# AlarisHandV1.net
KiCad netlist of a schematic drawn in EAGLE
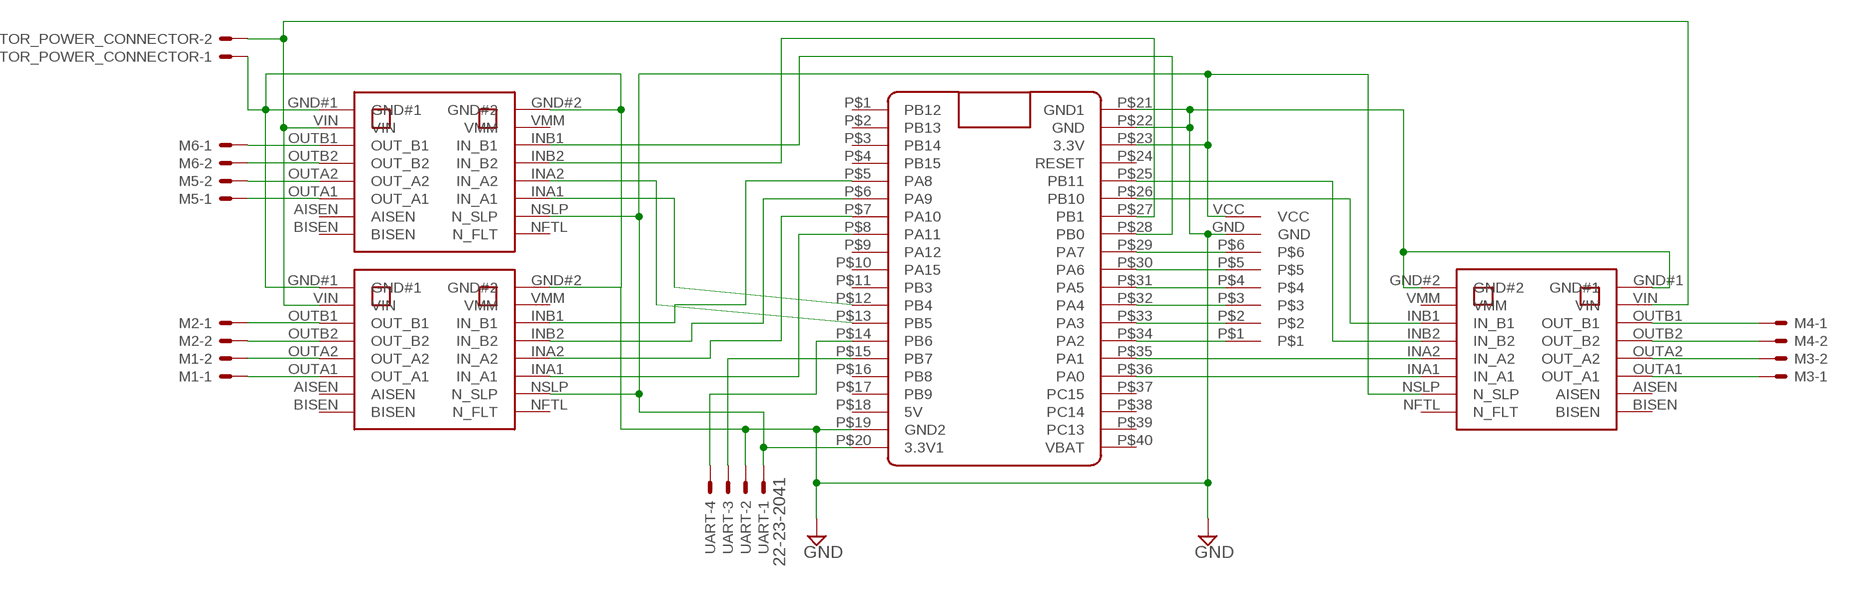
[diagram p0: schematic, sheet 1]

(export (version "E")
  (design (tool "Eeschema 10.0.6"))
  (components
    (comp (ref "M1")
      (value "22-23-2021")
      (footprint "eagle-import:22-23-2021")
      (fields (field (name "MF") "MOLEX"))
      (libsource (lib "eagle-import") (part "22-23-2021"))
    )
    (comp (ref "M2")
      (value "22-23-2021")
      (footprint "eagle-import:22-23-2021")
      (fields (field (name "MF") "MOLEX"))
      (libsource (lib "eagle-import") (part "22-23-2021"))
    )
    (comp (ref "M3")
      (value "22-23-2021")
      (footprint "eagle-import:22-23-2021")
      (fields (field (name "MF") "MOLEX"))
      (libsource (lib "eagle-import") (part "22-23-2021"))
    )
    (comp (ref "M4")
      (value "22-23-2021")
      (footprint "eagle-import:22-23-2021")
      (fields (field (name "MF") "MOLEX"))
      (libsource (lib "eagle-import") (part "22-23-2021"))
    )
    (comp (ref "M5")
      (value "22-23-2021")
      (footprint "eagle-import:22-23-2021")
      (fields (field (name "MF") "MOLEX"))
      (libsource (lib "eagle-import") (part "22-23-2021"))
    )
    (comp (ref "M6")
      (value "22-23-2021")
      (footprint "eagle-import:22-23-2021")
      (fields (field (name "MF") "MOLEX"))
      (libsource (lib "eagle-import") (part "22-23-2021"))
    )
    (comp (ref "MOTOR_POWER_CONNECTOR")
      (value "22-23-2021")
      (footprint "eagle-import:22-23-2021")
      (fields (field (name "MF") "MOLEX"))
      (libsource (lib "eagle-import") (part "con-molex_165_22-23-2021"))
    )
    (comp (ref "U$1")
      (value "POLOLUDRV8833")
      (footprint "eagle-import:POLOLUDRV8833")
      (libsource (lib "eagle-import") (part "POLOLUDRV8833"))
    )
    (comp (ref "U$2")
      (value "POLOLUDRV8833")
      (footprint "eagle-import:POLOLUDRV8833")
      (libsource (lib "eagle-import") (part "POLOLUDRV8833"))
    )
    (comp (ref "U$3")
      (value "POLOLUDRV8833")
      (footprint "eagle-import:POLOLUDRV8833")
      (libsource (lib "eagle-import") (part "POLOLUDRV8833"))
    )
    (comp (ref "U$4")
      (value "BLUE_PILL")
      (footprint "eagle-import:BLUE_PILL")
      (libsource (lib "eagle-import") (part "BLUE_PILL"))
    )
    (comp (ref "U$5")
      (value "SENSOR_RAIL")
      (footprint "eagle-import:SENSOR_RAIL")
      (libsource (lib "eagle-import") (part "SENSOR_RAIL"))
    )
    (comp (ref "UART")
      (value "22-23-2041")
      (footprint "eagle-import:22-23-2041")
      (fields (field (name "MF") "MOLEX"))
      (libsource (lib "eagle-import") (part "22-23-2041"))
    )
  )
  (nets
    (net (code "1") (name "GND") (class "Default")
      (node (ref "MOTOR_POWER_CONNECTOR") (pin "1") (pinfunction "S_1") (pintype "passive"))
      (node (ref "U$1") (pin "GND#1") (pinfunction "GND#1_GND#1") (pintype "bidirectional"))
      (node (ref "U$1") (pin "GND#2") (pinfunction "GND#2_GND#2") (pintype "bidirectional"))
      (node (ref "U$2") (pin "GND#1") (pinfunction "GND#1_GND#1") (pintype "bidirectional"))
      (node (ref "U$2") (pin "GND#2") (pinfunction "GND#2_GND#2") (pintype "bidirectional"))
      (node (ref "U$3") (pin "GND#1") (pinfunction "GND#1_GND#1") (pintype "bidirectional"))
      (node (ref "U$3") (pin "GND#2") (pinfunction "GND#2_GND#2") (pintype "bidirectional"))
      (node (ref "U$4") (pin "P$19") (pinfunction "GND2_P$19") (pintype "bidirectional"))
      (node (ref "U$4") (pin "P$21") (pinfunction "GND1_P$21") (pintype "power_in"))
      (node (ref "U$4") (pin "P$22") (pinfunction "GND_P$22") (pintype "bidirectional"))
      (node (ref "U$5") (pin "GND") (pinfunction "GND_GND") (pintype "bidirectional"))
      (node (ref "UART") (pin "2") (pinfunction "S_2") (pintype "passive"))
    )
    (net (code "2") (name "Net-(M1A-S)") (class "Default")
      (node (ref "M1") (pin "1") (pinfunction "S_1") (pintype "passive"))
      (node (ref "U$1") (pin "OUTA1") (pinfunction "OUT_A1_OUTA1") (pintype "bidirectional"))
    )
    (net (code "3") (name "Net-(M1B-S)") (class "Default")
      (node (ref "M1") (pin "2") (pinfunction "S_2") (pintype "passive"))
      (node (ref "U$1") (pin "OUTA2") (pinfunction "OUT_A2_OUTA2") (pintype "bidirectional"))
    )
    (net (code "4") (name "Net-(M2A-S)") (class "Default")
      (node (ref "M2") (pin "1") (pinfunction "S_1") (pintype "passive"))
      (node (ref "U$1") (pin "OUTB1") (pinfunction "OUT_B1_OUTB1") (pintype "bidirectional"))
    )
    (net (code "5") (name "Net-(M2B-S)") (class "Default")
      (node (ref "M2") (pin "2") (pinfunction "S_2") (pintype "passive"))
      (node (ref "U$1") (pin "OUTB2") (pinfunction "OUT_B2_OUTB2") (pintype "bidirectional"))
    )
    (net (code "6") (name "Net-(M3A-S)") (class "Default")
      (node (ref "M3") (pin "1") (pinfunction "S_1") (pintype "passive"))
      (node (ref "U$3") (pin "OUTA1") (pinfunction "OUT_A1_OUTA1") (pintype "bidirectional"))
    )
    (net (code "7") (name "Net-(M3B-S)") (class "Default")
      (node (ref "M3") (pin "2") (pinfunction "S_2") (pintype "passive"))
      (node (ref "U$3") (pin "OUTA2") (pinfunction "OUT_A2_OUTA2") (pintype "bidirectional"))
    )
    (net (code "8") (name "Net-(M4A-S)") (class "Default")
      (node (ref "M4") (pin "1") (pinfunction "S_1") (pintype "passive"))
      (node (ref "U$3") (pin "OUTB1") (pinfunction "OUT_B1_OUTB1") (pintype "bidirectional"))
    )
    (net (code "9") (name "Net-(M4B-S)") (class "Default")
      (node (ref "M4") (pin "2") (pinfunction "S_2") (pintype "passive"))
      (node (ref "U$3") (pin "OUTB2") (pinfunction "OUT_B2_OUTB2") (pintype "bidirectional"))
    )
    (net (code "10") (name "Net-(M5A-S)") (class "Default")
      (node (ref "M5") (pin "1") (pinfunction "S_1") (pintype "passive"))
      (node (ref "U$2") (pin "OUTA1") (pinfunction "OUT_A1_OUTA1") (pintype "bidirectional"))
    )
    (net (code "11") (name "Net-(M5B-S)") (class "Default")
      (node (ref "M5") (pin "2") (pinfunction "S_2") (pintype "passive"))
      (node (ref "U$2") (pin "OUTA2") (pinfunction "OUT_A2_OUTA2") (pintype "bidirectional"))
    )
    (net (code "12") (name "Net-(M6A-S)") (class "Default")
      (node (ref "M6") (pin "1") (pinfunction "S_1") (pintype "passive"))
      (node (ref "U$2") (pin "OUTB1") (pinfunction "OUT_B1_OUTB1") (pintype "bidirectional"))
    )
    (net (code "13") (name "Net-(M6B-S)") (class "Default")
      (node (ref "M6") (pin "2") (pinfunction "S_2") (pintype "passive"))
      (node (ref "U$2") (pin "OUTB2") (pinfunction "OUT_B2_OUTB2") (pintype "bidirectional"))
    )
    (net (code "14") (name "Net-(MOTOR_POWER_CONNECTORB-S)") (class "Default")
      (node (ref "MOTOR_POWER_CONNECTOR") (pin "2") (pinfunction "S_2") (pintype "passive"))
      (node (ref "U$1") (pin "VIN") (pinfunction "VIN_VIN") (pintype "bidirectional"))
      (node (ref "U$2") (pin "VIN") (pinfunction "VIN_VIN") (pintype "bidirectional"))
      (node (ref "U$3") (pin "VIN") (pinfunction "VIN_VIN") (pintype "bidirectional"))
    )
    (net (code "15") (name "Net-(U$1-IN_A1)") (class "Default")
      (node (ref "U$1") (pin "INA1") (pinfunction "IN_A1_INA1") (pintype "bidirectional"))
      (node (ref "U$4") (pin "P$8") (pinfunction "PA11_P$8") (pintype "bidirectional"))
    )
    (net (code "16") (name "Net-(U$1-IN_A2)") (class "Default")
      (node (ref "U$1") (pin "INA2") (pinfunction "IN_A2_INA2") (pintype "bidirectional"))
      (node (ref "U$4") (pin "P$7") (pinfunction "PA10_P$7") (pintype "bidirectional"))
    )
    (net (code "17") (name "Net-(U$1-IN_B1)") (class "Default")
      (node (ref "U$1") (pin "INB1") (pinfunction "IN_B1_INB1") (pintype "bidirectional"))
      (node (ref "U$4") (pin "P$5") (pinfunction "PA8_P$5") (pintype "bidirectional"))
    )
    (net (code "18") (name "Net-(U$1-IN_B2)") (class "Default")
      (node (ref "U$1") (pin "INB2") (pinfunction "IN_B2_INB2") (pintype "bidirectional"))
      (node (ref "U$4") (pin "P$6") (pinfunction "PA9_P$6") (pintype "bidirectional"))
    )
    (net (code "19") (name "Net-(U$1-N_SLP)") (class "Default")
      (node (ref "U$1") (pin "NSLP") (pinfunction "N_SLP_NSLP") (pintype "bidirectional"))
      (node (ref "U$2") (pin "NSLP") (pinfunction "N_SLP_NSLP") (pintype "bidirectional"))
      (node (ref "U$3") (pin "NSLP") (pinfunction "N_SLP_NSLP") (pintype "bidirectional"))
      (node (ref "U$4") (pin "P$20") (pinfunction "3.3V1_P$20") (pintype "bidirectional"))
      (node (ref "U$4") (pin "P$23") (pinfunction "3.3V_P$23") (pintype "bidirectional"))
      (node (ref "U$5") (pin "VCC") (pinfunction "VCC_VCC") (pintype "bidirectional"))
      (node (ref "UART") (pin "1") (pinfunction "S_1") (pintype "passive"))
    )
    (net (code "20") (name "Net-(U$2-IN_A1)") (class "Default")
      (node (ref "U$2") (pin "INA1") (pinfunction "IN_A1_INA1") (pintype "bidirectional"))
      (node (ref "U$4") (pin "P$12") (pinfunction "PB4_P$12") (pintype "bidirectional"))
    )
    (net (code "21") (name "Net-(U$2-IN_A2)") (class "Default")
      (node (ref "U$2") (pin "INA2") (pinfunction "IN_A2_INA2") (pintype "bidirectional"))
      (node (ref "U$4") (pin "P$13") (pinfunction "PB5_P$13") (pintype "bidirectional"))
    )
    (net (code "22") (name "Net-(U$2-IN_B1)") (class "Default")
      (node (ref "U$2") (pin "INB1") (pinfunction "IN_B1_INB1") (pintype "bidirectional"))
      (node (ref "U$4") (pin "P$28") (pinfunction "PB0_P$28") (pintype "bidirectional"))
    )
    (net (code "23") (name "Net-(U$2-IN_B2)") (class "Default")
      (node (ref "U$2") (pin "INB2") (pinfunction "IN_B2_INB2") (pintype "bidirectional"))
      (node (ref "U$4") (pin "P$27") (pinfunction "PB1_P$27") (pintype "bidirectional"))
    )
    (net (code "24") (name "Net-(U$3-IN_A1)") (class "Default")
      (node (ref "U$3") (pin "INA1") (pinfunction "IN_A1_INA1") (pintype "bidirectional"))
      (node (ref "U$4") (pin "P$36") (pinfunction "PA0_P$36") (pintype "bidirectional"))
    )
    (net (code "25") (name "Net-(U$3-IN_A2)") (class "Default")
      (node (ref "U$3") (pin "INA2") (pinfunction "IN_A2_INA2") (pintype "bidirectional"))
      (node (ref "U$4") (pin "P$35") (pinfunction "PA1_P$35") (pintype "bidirectional"))
    )
    (net (code "26") (name "Net-(U$3-IN_B1)") (class "Default")
      (node (ref "U$3") (pin "INB1") (pinfunction "IN_B1_INB1") (pintype "bidirectional"))
      (node (ref "U$4") (pin "P$26") (pinfunction "PB10_P$26") (pintype "bidirectional"))
    )
    (net (code "27") (name "Net-(U$3-IN_B2)") (class "Default")
      (node (ref "U$3") (pin "INB2") (pinfunction "IN_B2_INB2") (pintype "bidirectional"))
      (node (ref "U$4") (pin "P$25") (pinfunction "PB11_P$25") (pintype "bidirectional"))
    )
    (net (code "28") (name "Net-(U$4-PA2)") (class "Default")
      (node (ref "U$4") (pin "P$34") (pinfunction "PA2_P$34") (pintype "bidirectional"))
      (node (ref "U$5") (pin "P$1") (pinfunction "P$1_P$1") (pintype "bidirectional"))
    )
    (net (code "29") (name "Net-(U$4-PA3)") (class "Default")
      (node (ref "U$4") (pin "P$33") (pinfunction "PA3_P$33") (pintype "bidirectional"))
      (node (ref "U$5") (pin "P$2") (pinfunction "P$2_P$2") (pintype "bidirectional"))
    )
    (net (code "30") (name "Net-(U$4-PA4)") (class "Default")
      (node (ref "U$4") (pin "P$32") (pinfunction "PA4_P$32") (pintype "bidirectional"))
      (node (ref "U$5") (pin "P$3") (pinfunction "P$3_P$3") (pintype "bidirectional"))
    )
    (net (code "31") (name "Net-(U$4-PA5)") (class "Default")
      (node (ref "U$4") (pin "P$31") (pinfunction "PA5_P$31") (pintype "bidirectional"))
      (node (ref "U$5") (pin "P$4") (pinfunction "P$4_P$4") (pintype "bidirectional"))
    )
    (net (code "32") (name "Net-(U$4-PA6)") (class "Default")
      (node (ref "U$4") (pin "P$30") (pinfunction "PA6_P$30") (pintype "bidirectional"))
      (node (ref "U$5") (pin "P$5") (pinfunction "P$5_P$5") (pintype "bidirectional"))
    )
    (net (code "33") (name "Net-(U$4-PA7)") (class "Default")
      (node (ref "U$4") (pin "P$29") (pinfunction "PA7_P$29") (pintype "bidirectional"))
      (node (ref "U$5") (pin "P$6") (pinfunction "P$6_P$6") (pintype "bidirectional"))
    )
    (net (code "34") (name "Net-(U$4-PB6)") (class "Default")
      (node (ref "U$4") (pin "P$14") (pinfunction "PB6_P$14") (pintype "bidirectional"))
      (node (ref "UART") (pin "4") (pinfunction "S_4") (pintype "passive"))
    )
    (net (code "35") (name "Net-(U$4-PB7)") (class "Default")
      (node (ref "U$4") (pin "P$15") (pinfunction "PB7_P$15") (pintype "bidirectional"))
      (node (ref "UART") (pin "3") (pinfunction "S_3") (pintype "passive"))
    )
    (net (code "36") (name "unconnected-(U$1-N_FLT-PadNFTL)") (class "Default")
      (node (ref "U$1") (pin "NFTL") (pinfunction "N_FLT_NFTL") (pintype "bidirectional"))
    )
    (net (code "37") (name "unconnected-(U$1-PadAISEN)") (class "Default")
      (node (ref "U$1") (pin "AISEN") (pinfunction "AISEN_AISEN") (pintype "bidirectional"))
    )
    (net (code "38") (name "unconnected-(U$1-PadBISEN)") (class "Default")
      (node (ref "U$1") (pin "BISEN") (pinfunction "BISEN_BISEN") (pintype "bidirectional"))
    )
    (net (code "39") (name "unconnected-(U$1-PadVMM)") (class "Default")
      (node (ref "U$1") (pin "VMM") (pinfunction "VMM_VMM") (pintype "bidirectional"))
    )
    (net (code "40") (name "unconnected-(U$2-N_FLT-PadNFTL)") (class "Default")
      (node (ref "U$2") (pin "NFTL") (pinfunction "N_FLT_NFTL") (pintype "bidirectional"))
    )
    (net (code "41") (name "unconnected-(U$2-PadAISEN)") (class "Default")
      (node (ref "U$2") (pin "AISEN") (pinfunction "AISEN_AISEN") (pintype "bidirectional"))
    )
    (net (code "42") (name "unconnected-(U$2-PadBISEN)") (class "Default")
      (node (ref "U$2") (pin "BISEN") (pinfunction "BISEN_BISEN") (pintype "bidirectional"))
    )
    (net (code "43") (name "unconnected-(U$2-PadVMM)") (class "Default")
      (node (ref "U$2") (pin "VMM") (pinfunction "VMM_VMM") (pintype "bidirectional"))
    )
    (net (code "44") (name "unconnected-(U$3-N_FLT-PadNFTL)") (class "Default")
      (node (ref "U$3") (pin "NFTL") (pinfunction "N_FLT_NFTL") (pintype "bidirectional"))
    )
    (net (code "45") (name "unconnected-(U$3-PadAISEN)") (class "Default")
      (node (ref "U$3") (pin "AISEN") (pinfunction "AISEN_AISEN") (pintype "bidirectional"))
    )
    (net (code "46") (name "unconnected-(U$3-PadBISEN)") (class "Default")
      (node (ref "U$3") (pin "BISEN") (pinfunction "BISEN_BISEN") (pintype "bidirectional"))
    )
    (net (code "47") (name "unconnected-(U$3-PadVMM)") (class "Default")
      (node (ref "U$3") (pin "VMM") (pinfunction "VMM_VMM") (pintype "bidirectional"))
    )
    (net (code "48") (name "unconnected-(U$4-5V-PadP$18)") (class "Default")
      (node (ref "U$4") (pin "P$18") (pinfunction "5V_P$18") (pintype "bidirectional"))
    )
    (net (code "49") (name "unconnected-(U$4-PA12-PadP$9)") (class "Default")
      (node (ref "U$4") (pin "P$9") (pinfunction "PA12_P$9") (pintype "bidirectional"))
    )
    (net (code "50") (name "unconnected-(U$4-PA15-PadP$10)") (class "Default")
      (node (ref "U$4") (pin "P$10") (pinfunction "PA15_P$10") (pintype "bidirectional"))
    )
    (net (code "51") (name "unconnected-(U$4-PB3-PadP$11)") (class "Default")
      (node (ref "U$4") (pin "P$11") (pinfunction "PB3_P$11") (pintype "bidirectional"))
    )
    (net (code "52") (name "unconnected-(U$4-PB8-PadP$16)") (class "Default")
      (node (ref "U$4") (pin "P$16") (pinfunction "PB8_P$16") (pintype "bidirectional"))
    )
    (net (code "53") (name "unconnected-(U$4-PB9-PadP$17)") (class "Default")
      (node (ref "U$4") (pin "P$17") (pinfunction "PB9_P$17") (pintype "bidirectional"))
    )
    (net (code "54") (name "unconnected-(U$4-PB12-PadP$1)") (class "Default")
      (node (ref "U$4") (pin "P$1") (pinfunction "PB12_P$1") (pintype "bidirectional"))
    )
    (net (code "55") (name "unconnected-(U$4-PB13-PadP$2)") (class "Default")
      (node (ref "U$4") (pin "P$2") (pinfunction "PB13_P$2") (pintype "bidirectional"))
    )
    (net (code "56") (name "unconnected-(U$4-PB14-PadP$3)") (class "Default")
      (node (ref "U$4") (pin "P$3") (pinfunction "PB14_P$3") (pintype "bidirectional"))
    )
    (net (code "57") (name "unconnected-(U$4-PB15-PadP$4)") (class "Default")
      (node (ref "U$4") (pin "P$4") (pinfunction "PB15_P$4") (pintype "bidirectional"))
    )
    (net (code "58") (name "unconnected-(U$4-PC13-PadP$39)") (class "Default")
      (node (ref "U$4") (pin "P$39") (pinfunction "PC13_P$39") (pintype "bidirectional"))
    )
    (net (code "59") (name "unconnected-(U$4-PC14-PadP$38)") (class "Default")
      (node (ref "U$4") (pin "P$38") (pinfunction "PC14_P$38") (pintype "bidirectional"))
    )
    (net (code "60") (name "unconnected-(U$4-PC15-PadP$37)") (class "Default")
      (node (ref "U$4") (pin "P$37") (pinfunction "PC15_P$37") (pintype "bidirectional"))
    )
    (net (code "61") (name "unconnected-(U$4-RESET-PadP$24)") (class "Default")
      (node (ref "U$4") (pin "P$24") (pinfunction "RESET_P$24") (pintype "bidirectional"))
    )
    (net (code "62") (name "unconnected-(U$4-VBAT-PadP$40)") (class "Default")
      (node (ref "U$4") (pin "P$40") (pinfunction "VBAT_P$40") (pintype "bidirectional"))
    )
  )
)
